# RS2-708_V010.net
KiCad netlist of a schematic drawn in Altium Designer
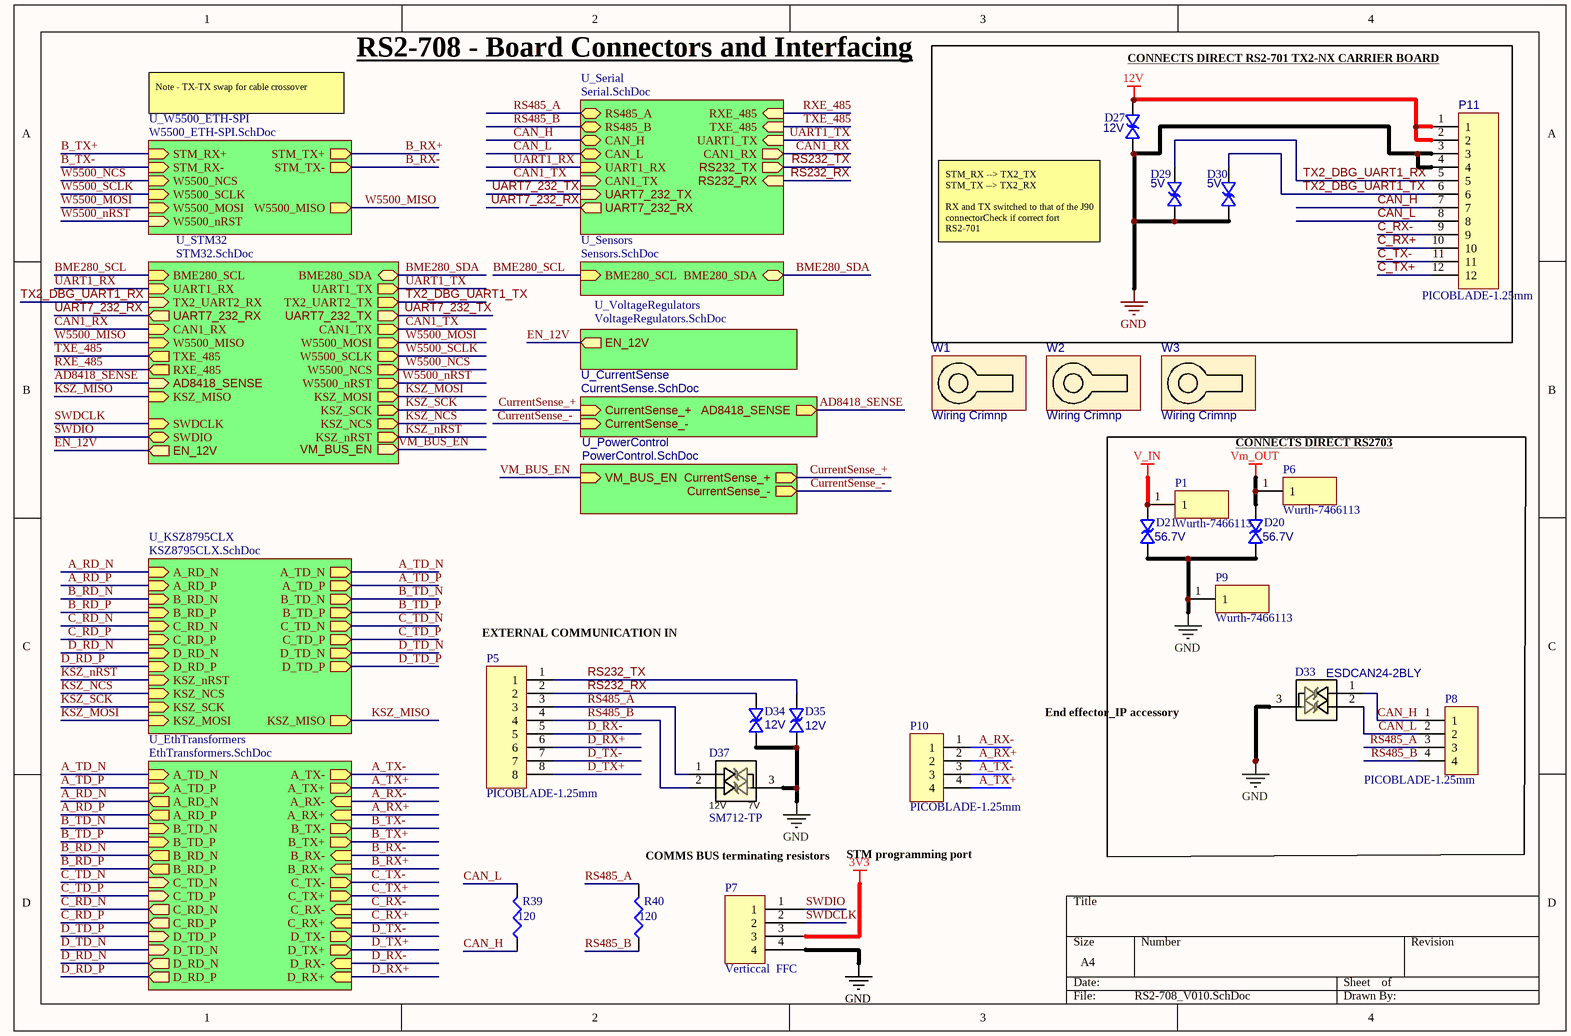
[diagram p0: RS2-708_V010.SchDoc]

(export (version "E")
  (design (tool "Eeschema 10.0.6"))
  (components
    (comp (ref "D20")
      (value "TVS-Bidirectional")
      (footprint "DO-214AB")
      (fields (field (name "REVERSE BREAKDOWN VOLTAGE") "56.7V"))
      (libsource (lib "BPL-ShematicLibrary") (part "TVS-Bidirectional"))
    )
    (comp (ref "D21")
      (value "TVS-Bidirectional")
      (footprint "DO-214AB")
      (fields (field (name "REVERSE BREAKDOWN VOLTAGE") "56.7V"))
      (libsource (lib "BPL-ShematicLibrary") (part "TVS-Bidirectional"))
    )
    (comp (ref "D27")
      (value "TVS-Bidirectional")
      (footprint "SLP1006P2T")
      (description "TVS DIODE 12V 27V SLP1006P2T")
      (fields (field (name "WORKING VOLTAGE") "12V"))
      (libsource (lib "BPL-ShematicLibrary") (part "TVS-Bidirectional"))
    )
    (comp (ref "D29")
      (value "TVS-Bidirectional")
      (footprint "SLP1006P2T")
      (description "TVS DIODE 5V 20V SLP1006P2T")
      (fields (field (name "REVERSE STANDOFF VOLTAGE") "5V"))
      (libsource (lib "") (part "TVS-Bidirectional_1"))
    )
    (comp (ref "D30")
      (value "TVS-Bidirectional")
      (footprint "SLP1006P2T")
      (description "TVS DIODE 5V 20V SLP1006P2T")
      (fields (field (name "REVERSE STANDOFF VOLTAGE") "5V"))
      (libsource (lib "") (part "TVS-Bidirectional_1"))
    )
    (comp (ref "D33")
      (value "TVS- 3-pin")
      (footprint "SOT23-BAT54")
      (description "ESD Suppressor TVS 24V Automotive 3-Pin SOT-23 T/R")
      (fields (field (name "MANUFACTURER PART NUMBER 1") "ESDCAN24-2BLY"))
      (libsource (lib "BPL-ShematicLibrary") (part "TVS- 3-pin"))
    )
    (comp (ref "D34")
      (value "TVS-Bidirectional")
      (footprint "SLP1006P2T")
      (description "TVS DIODE 12V 27V SLP1006P2T")
      (fields (field (name "WORKING VOLTAGE") "12V"))
      (libsource (lib "BPL-ShematicLibrary") (part "TVS-Bidirectional"))
    )
    (comp (ref "D35")
      (value "TVS-Bidirectional")
      (footprint "SLP1006P2T")
      (description "TVS DIODE 12V 27V SLP1006P2T")
      (fields (field (name "WORKING VOLTAGE") "12V"))
      (libsource (lib "BPL-ShematicLibrary") (part "TVS-Bidirectional"))
    )
    (comp (ref "D37")
      (value "SM712-TP")
      (footprint "SOT23-BAT54")
      (description "TVS DIODE 12V 21V SOT23")
      (libsource (lib "BPL-ShematicLibrary") (part "SM712-TP"))
    )
    (comp (ref "P1")
      (value "Wurth-7466113")
      (footprint "7466113_V2")
      (description "POWER ELEMENT SHANK")
      (libsource (lib "BPL-ShematicLibrary") (part "7466113"))
    )
    (comp (ref "P5")
      (value "PICOBLADE-1.25mm")
      (footprint "532617008")
      (description "8POS Picoblade 1.25mm")
      (fields (field (name "MANUFACTURER") "Molex") (field (name "MANUFACTURER PART NUMBER") "0532617008"))
      (libsource (lib "BPL-ShematicLibrary") (part "532617008"))
    )
    (comp (ref "P6")
      (value "Wurth-7466113")
      (footprint "7466113_V2")
      (description "POWER ELEMENT SHANK")
      (libsource (lib "BPL-ShematicLibrary") (part "7466113"))
    )
    (comp (ref "P7")
      (value "Verticcal  FFC")
      (footprint "AFC11-S04ICC-00")
      (description "4 pin FFC connector,0.5mm pitch, 0.5A")
      (fields (field (name "MANUFACTURER PART NUMBER") "AFC11-S04ICC-00"))
      (libsource (lib "BPL-ShematicLibrary") (part "AFC11-S04ICC-00"))
    )
    (comp (ref "P8")
      (value "PICOBLADE-1.25mm")
      (footprint "532617004")
      (description "4POS Picoblade 1.25mm")
      (fields (field (name "MANUFACTURER") "Molex") (field (name "MANUFACTURER PART NUMBER") "0532617004"))
      (libsource (lib "") (part "0532617004_1"))
    )
    (comp (ref "P9")
      (value "Wurth-7466113")
      (footprint "7466113_V2")
      (description "POWER ELEMENT SHANK")
      (libsource (lib "BPL-ShematicLibrary") (part "7466113"))
    )
    (comp (ref "P10")
      (value "PICOBLADE-1.25mm")
      (footprint "532617004")
      (description "4POS Picoblade 1.25mm")
      (fields (field (name "MANUFACTURER") "Molex") (field (name "MANUFACTURER PART NUMBER") "0532617004"))
      (libsource (lib "BPL-ShematicLibrary") (part "0532617004"))
    )
    (comp (ref "P11")
      (value "PICOBLADE-1.25mm")
      (footprint "532617012")
      (description "Conn.;  Rect/PCB;  Header;  W-to-B;  1.25mmPitch;  12 Cir.; SMT;  Rt. Angle;  PicoBlade")
      (libsource (lib "BPL-ShematicLibrary") (part "532611271"))
    )
    (comp (ref "R39")
      (value "120")
      (footprint "RES0805")
      (description "Resistor")
      (fields (field (name "Comment") "Res"))
      (libsource (lib "BPL-ShematicLibrary") (part "Resistor"))
    )
    (comp (ref "R40")
      (value "120")
      (footprint "RES0805")
      (description "Resistor")
      (fields (field (name "Comment") "Res"))
      (libsource (lib "BPL-ShematicLibrary") (part "Resistor"))
    )
    (comp (ref "W1")
      (value "Wiring Crimnp")
      (footprint "Power_M3_Eyelet_Up")
      (description "Wiring Crimp Connector")
      (libsource (lib "BPL-ShematicLibrary") (part "Wiring_CrimpConnector"))
    )
    (comp (ref "W2")
      (value "Wiring Crimnp")
      (footprint "Power_M3_Eyelet_Up")
      (description "Wiring Crimp Connector")
      (libsource (lib "BPL-ShematicLibrary") (part "Wiring_CrimpConnector"))
    )
    (comp (ref "W3")
      (value "Wiring Crimnp")
      (footprint "Power_M3_Eyelet_Up")
      (description "Wiring Crimp Connector")
      (libsource (lib "BPL-ShematicLibrary") (part "Wiring_CrimpConnector"))
    )
  )
  (nets
    (net (code "4") (name "/A_RX+") (class "Default")
      (node (ref "P10") (pin "2") (pinfunction "2_2") (pintype "passive"))
    )
    (net (code "5") (name "/A_RX-") (class "Default")
      (node (ref "P10") (pin "1") (pinfunction "1_1") (pintype "passive"))
    )
    (net (code "8") (name "/A_TX+") (class "Default")
      (node (ref "P10") (pin "4") (pinfunction "4_4") (pintype "passive"))
    )
    (net (code "9") (name "/A_TX-") (class "Default")
      (node (ref "P10") (pin "3") (pinfunction "3_3") (pintype "passive"))
    )
    (net (code "22") (name "/CAN_H") (class "Default")
      (node (ref "D33") (pin "1") (pinfunction "1_1") (pintype "passive"))
      (node (ref "P11") (pin "7") (pinfunction "7_7") (pintype "passive"))
      (node (ref "P8") (pin "1") (pinfunction "1_1") (pintype "passive"))
      (node (ref "R39") (pin "1") (pinfunction "1_1") (pintype "passive"))
    )
    (net (code "23") (name "/CAN_L") (class "Default")
      (node (ref "D33") (pin "2") (pinfunction "2_2") (pintype "passive"))
      (node (ref "P11") (pin "8") (pinfunction "8_8") (pintype "passive"))
      (node (ref "P8") (pin "2") (pinfunction "2_2") (pintype "passive"))
      (node (ref "R39") (pin "2") (pinfunction "2_2") (pintype "passive"))
    )
    (net (code "26") (name "/C_RX+") (class "Default")
      (node (ref "P11") (pin "10") (pinfunction "10_10") (pintype "passive"))
    )
    (net (code "27") (name "/C_RX-") (class "Default")
      (node (ref "P11") (pin "9") (pinfunction "9_9") (pintype "passive"))
    )
    (net (code "30") (name "/C_TX+") (class "Default")
      (node (ref "P11") (pin "12") (pinfunction "12_12") (pintype "passive"))
    )
    (net (code "31") (name "/C_TX-") (class "Default")
      (node (ref "P11") (pin "11") (pinfunction "11_11") (pintype "passive"))
    )
    (net (code "36") (name "/D_RX+") (class "Default")
      (node (ref "P5") (pin "6") (pinfunction "6_6") (pintype "passive"))
    )
    (net (code "37") (name "/D_RX-") (class "Default")
      (node (ref "P5") (pin "5") (pinfunction "5_5") (pintype "passive"))
    )
    (net (code "40") (name "/D_TX+") (class "Default")
      (node (ref "P5") (pin "8") (pinfunction "8_8") (pintype "passive"))
    )
    (net (code "41") (name "/D_TX-") (class "Default")
      (node (ref "P5") (pin "7") (pinfunction "7_7") (pintype "passive"))
    )
    (net (code "48") (name "/RS232_RX") (class "Default")
      (node (ref "D34") (pin "2") (pinfunction "2_2") (pintype "passive"))
      (node (ref "P5") (pin "2") (pinfunction "2_2") (pintype "passive"))
    )
    (net (code "49") (name "/RS232_TX") (class "Default")
      (node (ref "D35") (pin "2") (pinfunction "2_2") (pintype "passive"))
      (node (ref "P5") (pin "1") (pinfunction "1_1") (pintype "passive"))
    )
    (net (code "50") (name "/RS485_A") (class "Default")
      (node (ref "D37") (pin "1") (pinfunction "1_1") (pintype "passive"))
      (node (ref "P5") (pin "3") (pinfunction "3_3") (pintype "passive"))
      (node (ref "P8") (pin "3") (pinfunction "3_3") (pintype "passive"))
      (node (ref "R40") (pin "2") (pinfunction "2_2") (pintype "passive"))
    )
    (net (code "51") (name "/RS485_B") (class "Default")
      (node (ref "D37") (pin "2") (pinfunction "2_2") (pintype "passive"))
      (node (ref "P5") (pin "4") (pinfunction "4_4") (pintype "passive"))
      (node (ref "P8") (pin "4") (pinfunction "4_4") (pintype "passive"))
      (node (ref "R40") (pin "1") (pinfunction "1_1") (pintype "passive"))
    )
    (net (code "53") (name "/SWDCLK") (class "Default")
      (node (ref "P7") (pin "2") (pinfunction "2_2") (pintype "passive"))
    )
    (net (code "54") (name "/SWDIO") (class "Default")
      (node (ref "P7") (pin "1") (pinfunction "1_1") (pintype "passive"))
    )
    (net (code "55") (name "/TX2_DBG_UART1_RX") (class "Default")
      (node (ref "D29") (pin "1") (pinfunction "1_1") (pintype "passive"))
      (node (ref "P11") (pin "5") (pinfunction "5_5") (pintype "passive"))
    )
    (net (code "56") (name "/TX2_DBG_UART1_TX") (class "Default")
      (node (ref "D30") (pin "1") (pinfunction "1_1") (pintype "passive"))
      (node (ref "P11") (pin "6") (pinfunction "6_6") (pintype "passive"))
    )
    (net (code "68") (name "3V3") (class "Default")
      (node (ref "P7") (pin "3") (pinfunction "3_3") (pintype "passive"))
    )
    (net (code "69") (name "12V") (class "Default")
      (node (ref "D27") (pin "2") (pinfunction "2_2") (pintype "passive"))
      (node (ref "P11") (pin "1") (pinfunction "1_1") (pintype "passive"))
      (node (ref "P11") (pin "2") (pinfunction "2_2") (pintype "passive"))
    )
    (net (code "70") (name "GND") (class "Default")
      (node (ref "D20") (pin "1") (pinfunction "1_1") (pintype "passive"))
      (node (ref "D21") (pin "1") (pinfunction "1_1") (pintype "passive"))
      (node (ref "D27") (pin "1") (pinfunction "1_1") (pintype "passive"))
      (node (ref "D29") (pin "2") (pinfunction "2_2") (pintype "passive"))
      (node (ref "D30") (pin "2") (pinfunction "2_2") (pintype "passive"))
      (node (ref "D33") (pin "3") (pinfunction "3_3") (pintype "passive"))
      (node (ref "D34") (pin "1") (pinfunction "1_1") (pintype "passive"))
      (node (ref "D35") (pin "1") (pinfunction "1_1") (pintype "passive"))
      (node (ref "D37") (pin "3") (pinfunction "3_3") (pintype "passive"))
      (node (ref "P11") (pin "3") (pinfunction "3_3") (pintype "passive"))
      (node (ref "P11") (pin "4") (pinfunction "4_4") (pintype "passive"))
      (node (ref "P7") (pin "4") (pinfunction "4_4") (pintype "passive"))
      (node (ref "P9") (pin "1") (pinfunction "1_1") (pintype "passive"))
    )
    (net (code "71") (name "V_IN") (class "Default")
      (node (ref "D21") (pin "2") (pinfunction "2_2") (pintype "passive"))
      (node (ref "P1") (pin "1") (pinfunction "1_1") (pintype "passive"))
    )
    (net (code "72") (name "Vm_OUT") (class "Default")
      (node (ref "D20") (pin "2") (pinfunction "2_2") (pintype "passive"))
      (node (ref "P6") (pin "1") (pinfunction "1_1") (pintype "passive"))
    )
  )
)
